# powerboard.net
KiCad netlist of a schematic drawn in EAGLE
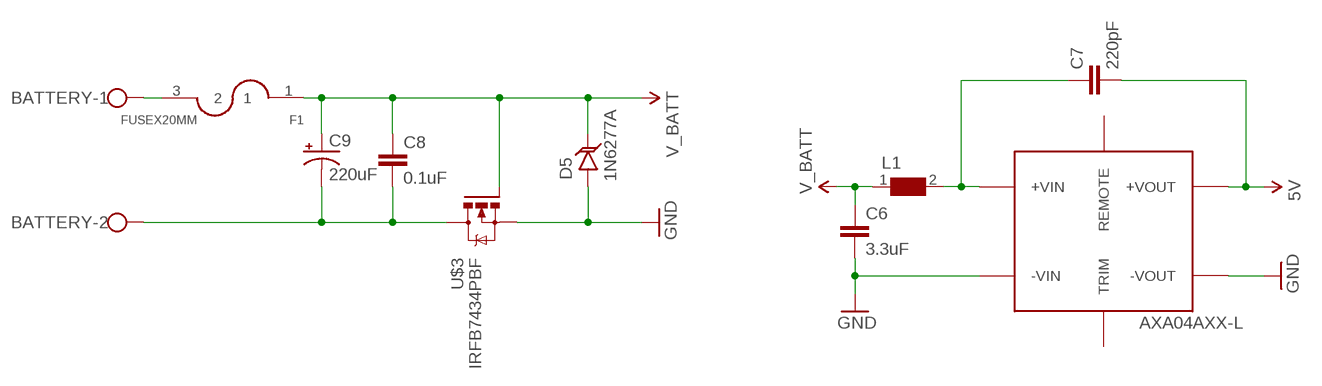
[diagram p0: schematic, sheet 1]

(export (version "E")
  (design (tool "Eeschema 10.0.6"))
  (components
    (comp (ref "BATTERY")
      (value "W237-102")
      (footprint "eagle-import:W237-102")
      (fields (field (name "MPN") "237-102"))
      (libsource (lib "eagle-import") (part "W237-102"))
    )
    (comp (ref "C6")
      (value "3.3uF")
      (footprint "eagle-import:1210")
      (libsource (lib "eagle-import") (part "CAP1210"))
    )
    (comp (ref "C7")
      (value "220pF")
      (footprint "eagle-import:C1808")
      (libsource (lib "eagle-import") (part "C-EUC1808"))
    )
    (comp (ref "C8")
      (value "0.1uF")
      (footprint "eagle-import:0603-CAP")
      (libsource (lib "eagle-import") (part "0.1UF-25V-5%(0603)"))
    )
    (comp (ref "C9")
      (value "220uF")
      (footprint "eagle-import:PANASONIC_G")
      (libsource (lib "eagle-import") (part "CPOL-USG"))
    )
    (comp (ref "D5")
      (value "1N6277A")
      (footprint "eagle-import:1N6277A")
      (libsource (lib "eagle-import") (part "1N6277A"))
    )
    (comp (ref "F1")
      (value "FUSEX20MM")
      (footprint "eagle-import:FUSE_5MM")
      (libsource (lib "eagle-import") (part "FUSEX20MM"))
    )
    (comp (ref "L1")
      (value "WE-HCI-744314650_7030/7040/7050")
      (footprint "eagle-import:WE-HCI_7030_7040_7050")
      (fields (field (name "MPN") "744314650"))
      (libsource (lib "eagle-import") (part "WE-HCI_7030/7040/7050-744314650"))
    )
    (comp (ref "U$2")
      (value "AXA04AXX-L")
      (footprint "eagle-import:AXA04AXX-L")
      (libsource (lib "eagle-import") (part "AXA04AXX-L"))
    )
    (comp (ref "U$3")
      (value "IRFB7434PBF")
      (footprint "eagle-import:IRFB7434PBF")
      (libsource (lib "eagle-import") (part "IRFB7434PBF"))
    )
  )
  (nets
    (net (code "1") (name "5V") (class "Default")
      (node (ref "C7") (pin "2") (pinfunction "2_2") (pintype "passive"))
      (node (ref "U$2") (pin "+VOUT") (pinfunction "+VOUT_+VOUT") (pintype "bidirectional"))
    )
    (net (code "2") (name "GND") (class "Default")
      (node (ref "C6") (pin "2") (pinfunction "2_2") (pintype "passive"))
      (node (ref "D5") (pin "A") (pinfunction "A_A") (pintype "passive"))
      (node (ref "U$2") (pin "-VIN") (pinfunction "-VIN_-VIN") (pintype "bidirectional"))
      (node (ref "U$2") (pin "-VOUT") (pinfunction "-VOUT_-VOUT") (pintype "bidirectional"))
      (node (ref "U$3") (pin "SOURCE") (pinfunction "S_SOURCE") (pintype "passive"))
    )
    (net (code "3") (name "Net-(BATTERYA-KL)") (class "Default")
      (node (ref "BATTERY") (pin "1") (pinfunction "KL_1") (pintype "passive"))
      (node (ref "F1") (pin "3") (pinfunction "2_3") (pintype "bidirectional"))
    )
    (net (code "4") (name "Net-(BATTERYB-KL)") (class "Default")
      (node (ref "BATTERY") (pin "2") (pinfunction "KL_2") (pintype "passive"))
      (node (ref "C8") (pin "2") (pinfunction "2_2") (pintype "passive"))
      (node (ref "C9") (pin "-") (pinfunction "-_-") (pintype "passive"))
      (node (ref "U$3") (pin "DRAIN") (pinfunction "D_DRAIN") (pintype "passive"))
    )
    (net (code "5") (name "Net-(C7-Pad1)") (class "Default")
      (node (ref "C7") (pin "1") (pinfunction "1_1") (pintype "passive"))
      (node (ref "L1") (pin "2") (pinfunction "2_2") (pintype "passive"))
      (node (ref "U$2") (pin "+VIN") (pinfunction "+VIN_+VIN") (pintype "bidirectional"))
    )
    (net (code "6") (name "V_BATT") (class "Default")
      (node (ref "C6") (pin "1") (pinfunction "1_1") (pintype "passive"))
      (node (ref "C8") (pin "1") (pinfunction "1_1") (pintype "passive"))
      (node (ref "C9") (pin "+") (pinfunction "+_+") (pintype "passive"))
      (node (ref "D5") (pin "C") (pinfunction "C_C") (pintype "passive"))
      (node (ref "F1") (pin "1") (pinfunction "1_1") (pintype "bidirectional"))
      (node (ref "L1") (pin "1") (pinfunction "1_1") (pintype "passive"))
      (node (ref "U$3") (pin "GATE") (pinfunction "G_GATE") (pintype "passive"))
    )
    (net (code "7") (name "unconnected-(U$2-PadREMOTE)") (class "Default")
      (node (ref "U$2") (pin "REMOTE") (pinfunction "REMOTE_REMOTE") (pintype "bidirectional"))
    )
    (net (code "8") (name "unconnected-(U$2-TRIM-PadTRIM{slash}COMMON)") (class "Default")
      (node (ref "U$2") (pin "TRIM/COMMON") (pinfunction "TRIM_TRIM/COMMON") (pintype "bidirectional"))
    )
  )
)
